# Medium_switch_HIGH_LOAD.net
KiCad netlist of a schematic drawn in EAGLE
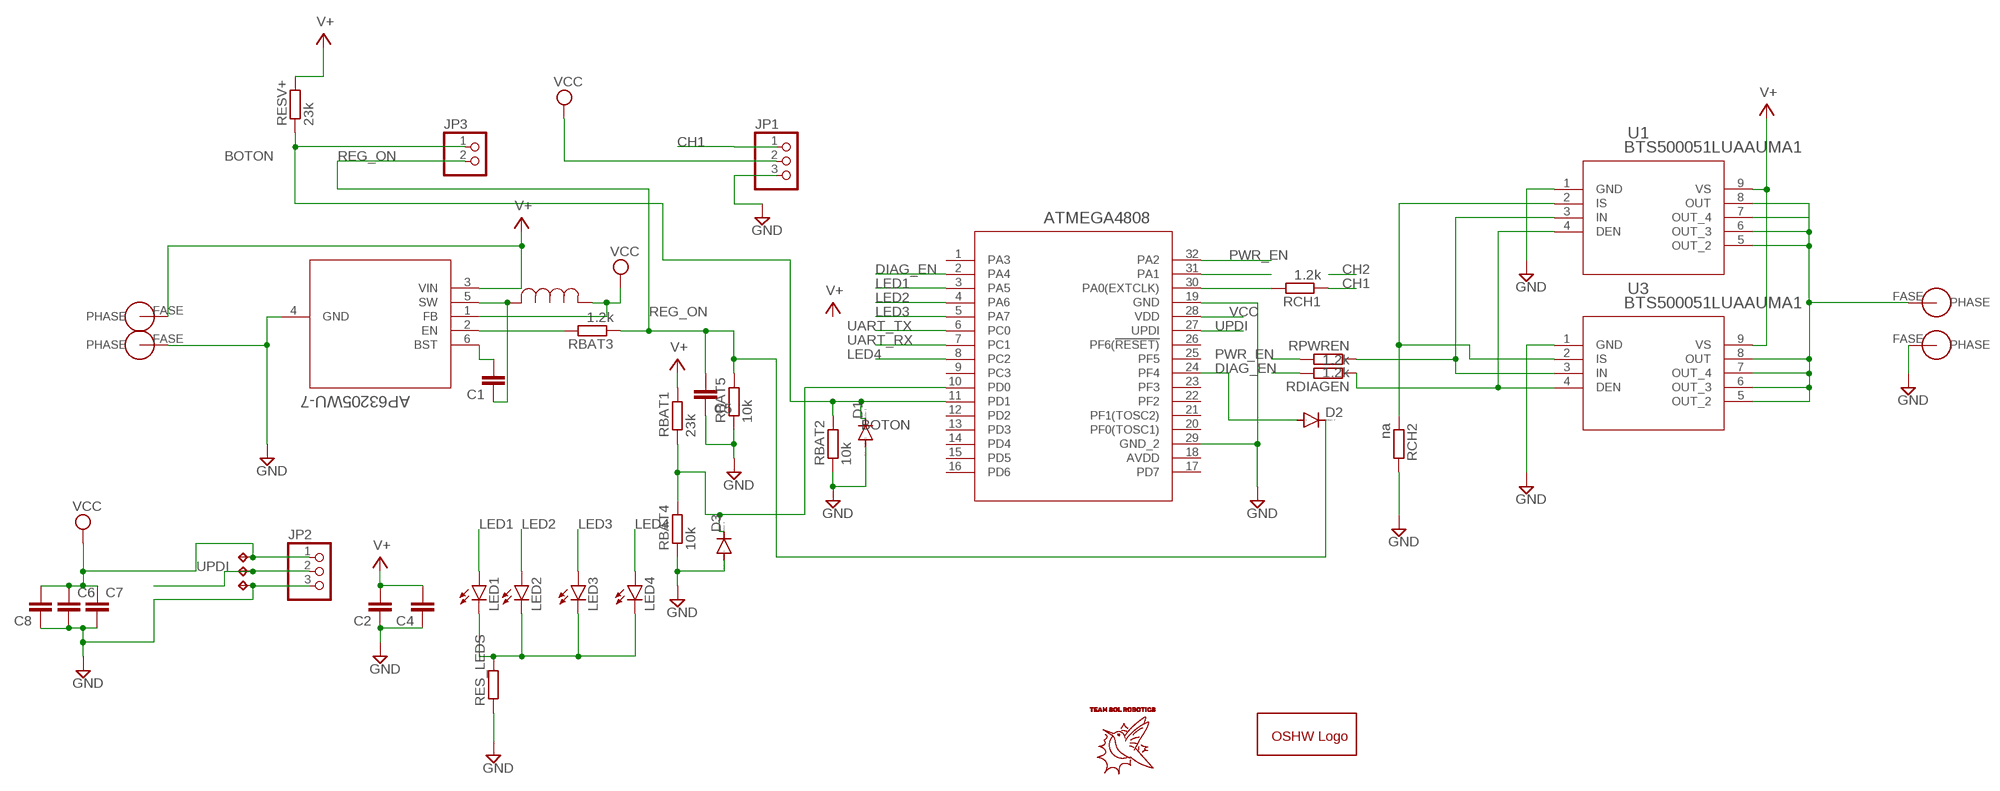
[diagram p0: schematic, sheet 1]

(export (version "E")
  (design (tool "Eeschema 10.0.6"))
  (components
    (comp (ref "BAT+")
      (value "PHASE")
      (footprint "eagle-import:POWEROUT")
      (libsource (lib "eagle-import") (part "PHASE"))
    )
    (comp (ref "C1")
      (value "C-EUC0402")
      (footprint "eagle-import:C0402")
      (libsource (lib "eagle-import") (part "C-EUC0402"))
    )
    (comp (ref "C2")
      (value "C-EUC1206")
      (footprint "eagle-import:C1206")
      (libsource (lib "eagle-import") (part "C-EUC1206"))
    )
    (comp (ref "C4")
      (value "C-EUC1206")
      (footprint "eagle-import:C1206")
      (libsource (lib "eagle-import") (part "C-EUC1206"))
    )
    (comp (ref "C5")
      (value "C-EUC0402")
      (footprint "eagle-import:C0402")
      (libsource (lib "eagle-import") (part "C-EUC0402"))
    )
    (comp (ref "C6")
      (value "C-EUC0805")
      (footprint "eagle-import:C0805")
      (libsource (lib "eagle-import") (part "C-EUC0805"))
    )
    (comp (ref "C7")
      (value "C-EUC0805")
      (footprint "eagle-import:C0805")
      (libsource (lib "eagle-import") (part "C-EUC0805"))
    )
    (comp (ref "C8")
      (value "C-EUC0402")
      (footprint "eagle-import:C0402")
      (libsource (lib "eagle-import") (part "C-EUC0402"))
    )
    (comp (ref "D1")
      (value "DIODE-MICROMELF-R")
      (footprint "eagle-import:MICROMELF-R")
      (libsource (lib "eagle-import") (part "DIODE-MICROMELF-R"))
    )
    (comp (ref "D2")
      (value "DIODE-MICROMELF-R")
      (footprint "eagle-import:MICROMELF-R")
      (libsource (lib "eagle-import") (part "DIODE-MICROMELF-R"))
    )
    (comp (ref "D3")
      (value "DIODE-MICROMELF-R")
      (footprint "eagle-import:MICROMELF-R")
      (libsource (lib "eagle-import") (part "DIODE-MICROMELF-R"))
    )
    (comp (ref "FASEA1")
      (value "PHASE")
      (footprint "eagle-import:POWEROUT")
      (libsource (lib "eagle-import") (part "PHASE"))
    )
    (comp (ref "FASEA3")
      (value "PHASE")
      (footprint "eagle-import:POWEROUT")
      (libsource (lib "eagle-import") (part "PHASE"))
    )
    (comp (ref "GOLD_ORB_SM1")
      (value "OSHWLOGOLOGO5MM")
      (footprint "eagle-import:OSHW_5MM")
      (libsource (lib "eagle-import") (part "OSHWLOGOLOGO5MM"))
    )
    (comp (ref "JP1")
      (value "PINHD-1X03_2.54-S")
      (footprint "eagle-import:1X03-S")
      (libsource (lib "eagle-import") (part "PINHD-1X03_2.54-S"))
    )
    (comp (ref "JP2")
      (value "PINHD-1X03_2.54-S")
      (footprint "eagle-import:1X03-S")
      (libsource (lib "eagle-import") (part "PINHD-1X03_2.54-S"))
    )
    (comp (ref "JP3")
      (value "PINHD-1X02_2.00")
      (footprint "eagle-import:1X02M")
      (libsource (lib "eagle-import") (part "PINHD-1X02_2.00"))
    )
    (comp (ref "LED1")
      (value "LEDSML0603")
      (footprint "eagle-import:SML0603")
      (libsource (lib "eagle-import") (part "LEDSML0603"))
    )
    (comp (ref "LED2")
      (value "LEDSML0603")
      (footprint "eagle-import:SML0603")
      (libsource (lib "eagle-import") (part "LEDSML0603"))
    )
    (comp (ref "LED3")
      (value "LEDSML0603")
      (footprint "eagle-import:SML0603")
      (libsource (lib "eagle-import") (part "LEDSML0603"))
    )
    (comp (ref "LED4")
      (value "LEDSML0603")
      (footprint "eagle-import:SML0603")
      (libsource (lib "eagle-import") (part "LEDSML0603"))
    )
    (comp (ref "OUTPUTPWR")
      (value "PHASE")
      (footprint "eagle-import:POWEROUT")
      (libsource (lib "eagle-import") (part "PHASE"))
    )
    (comp (ref "RBAT1")
      (value "23k")
      (footprint "eagle-import:R0603")
      (libsource (lib "eagle-import") (part "R-EU_R0603"))
    )
    (comp (ref "RBAT2")
      (value "10k")
      (footprint "eagle-import:R0603")
      (libsource (lib "eagle-import") (part "R-EU_R0603"))
    )
    (comp (ref "RBAT3")
      (value "1.2k")
      (footprint "eagle-import:R0603")
      (libsource (lib "eagle-import") (part "R-EU_R0603"))
    )
    (comp (ref "RBAT4")
      (value "10k")
      (footprint "eagle-import:R0603")
      (libsource (lib "eagle-import") (part "R-EU_R0603"))
    )
    (comp (ref "RBAT5")
      (value "10k")
      (footprint "eagle-import:R0603")
      (libsource (lib "eagle-import") (part "R-EU_R0603"))
    )
    (comp (ref "RCH1")
      (value "1.2k")
      (footprint "eagle-import:R0603")
      (libsource (lib "eagle-import") (part "R-EU_R0603"))
    )
    (comp (ref "RCH2")
      (value "na")
      (footprint "eagle-import:R0603")
      (libsource (lib "eagle-import") (part "R-EU_R0603"))
    )
    (comp (ref "RDIAGEN")
      (value "1.2k")
      (footprint "eagle-import:R0603")
      (libsource (lib "eagle-import") (part "R-EU_R0603"))
    )
    (comp (ref "RESV+")
      (value "23k")
      (footprint "eagle-import:R0603")
      (libsource (lib "eagle-import") (part "R-EU_R0603"))
    )
    (comp (ref "RES_LEDS")
      (value "R-EU_R0603")
      (footprint "eagle-import:R0603")
      (libsource (lib "eagle-import") (part "R-EU_R0603"))
    )
    (comp (ref "RPWREN")
      (value "1.2k")
      (footprint "eagle-import:R0603")
      (libsource (lib "eagle-import") (part "R-EU_R0603"))
    )
    (comp (ref "TP1")
      (value "TPTP13SQ")
      (footprint "eagle-import:TP13SQ")
      (libsource (lib "eagle-import") (part "TPTP13SQ"))
    )
    (comp (ref "TP2")
      (value "TPTP13SQ")
      (footprint "eagle-import:TP13SQ")
      (libsource (lib "eagle-import") (part "TPTP13SQ"))
    )
    (comp (ref "TP3")
      (value "TPTP13SQ")
      (footprint "eagle-import:TP13SQ")
      (libsource (lib "eagle-import") (part "TPTP13SQ"))
    )
    (comp (ref "U$1")
      (value "ATMEGA4808")
      (footprint "eagle-import:QFP80P900X900X120-32N")
      (libsource (lib "eagle-import") (part "ATMEGA4808"))
    )
    (comp (ref "U$3")
      (value "INDUCTOR4.7")
      (footprint "eagle-import:IND_NRS5030T100MMGJ_TAY")
      (libsource (lib "eagle-import") (part "INDUCTOR4.7"))
    )
    (comp (ref "U1")
      (value "BTS500051LUAAUMA1")
      (footprint "eagle-import:PG-HSOF-8_INF")
      (fields (field (name "COPYRIGHT") "Copyright (C) 2024 Ultra Librarian. All rights reserved."))
      (libsource (lib "eagle-import") (part "BTS500051LUAAUMA1"))
    )
    (comp (ref "U2")
      (value "AP63205WU-7")
      (footprint "eagle-import:SOIC_05WU-7_DIO")
      (fields (field (name "COPYRIGHT") "Copyright (C) 2018 Accelerated Designs. All rights reserved"))
      (libsource (lib "eagle-import") (part "AP63205WU-7"))
    )
    (comp (ref "U3")
      (value "BTS500051LUAAUMA1")
      (footprint "eagle-import:PG-HSOF-8_INF")
      (fields (field (name "COPYRIGHT") "Copyright (C) 2024 Ultra Librarian. All rights reserved."))
      (libsource (lib "eagle-import") (part "BTS500051LUAAUMA1"))
    )
  )
  (nets
    (net (code "1") (name "/AVDD") (class "Default")
      (node (ref "U$1") (pin "18") (pinfunction "AVDD_18") (pintype "power_in"))
    )
    (net (code "2") (name "/BOTON") (class "Default")
      (node (ref "D1") (pin "C") (pinfunction "C_C") (pintype "passive"))
      (node (ref "JP3") (pin "1") (pinfunction "1_1") (pintype "passive"))
      (node (ref "RBAT2") (pin "2") (pinfunction "2_2") (pintype "passive"))
      (node (ref "RESV+") (pin "1") (pinfunction "1_1") (pintype "passive"))
      (node (ref "U$1") (pin "11") (pinfunction "PD1_11") (pintype "bidirectional"))
    )
    (net (code "3") (name "/CH1") (class "Default")
      (node (ref "JP1") (pin "1") (pinfunction "1_1") (pintype "passive"))
      (node (ref "RCH1") (pin "1") (pinfunction "1_1") (pintype "passive"))
    )
    (net (code "5") (name "/DIAG_EN") (class "Default")
      (node (ref "RDIAGEN") (pin "2") (pinfunction "2_2") (pintype "passive"))
      (node (ref "U$1") (pin "2") (pinfunction "PA4_2") (pintype "bidirectional"))
    )
    (net (code "6") (name "/LED1") (class "Default")
      (node (ref "LED1") (pin "A") (pinfunction "A_A") (pintype "passive"))
      (node (ref "U$1") (pin "3") (pinfunction "PA5_3") (pintype "bidirectional"))
    )
    (net (code "7") (name "/LED2") (class "Default")
      (node (ref "LED2") (pin "A") (pinfunction "A_A") (pintype "passive"))
      (node (ref "U$1") (pin "4") (pinfunction "PA6_4") (pintype "bidirectional"))
    )
    (net (code "8") (name "/LED3") (class "Default")
      (node (ref "LED3") (pin "A") (pinfunction "A_A") (pintype "passive"))
      (node (ref "U$1") (pin "5") (pinfunction "PA7_5") (pintype "bidirectional"))
    )
    (net (code "9") (name "/LED4") (class "Default")
      (node (ref "LED4") (pin "A") (pinfunction "A_A") (pintype "passive"))
      (node (ref "U$1") (pin "8") (pinfunction "PC2_8") (pintype "bidirectional"))
    )
    (net (code "10") (name "/PWR_EN") (class "Default")
      (node (ref "RPWREN") (pin "2") (pinfunction "2_2") (pintype "passive"))
      (node (ref "U$1") (pin "32") (pinfunction "PA2_32") (pintype "bidirectional"))
    )
    (net (code "11") (name "/REG_ON") (class "Default")
      (node (ref "C5") (pin "2") (pinfunction "2_2") (pintype "passive"))
      (node (ref "D2") (pin "C") (pinfunction "C_C") (pintype "passive"))
      (node (ref "JP3") (pin "2") (pinfunction "2_2") (pintype "passive"))
      (node (ref "RBAT3") (pin "1") (pinfunction "1_1") (pintype "passive"))
      (node (ref "RBAT5") (pin "2") (pinfunction "2_2") (pintype "passive"))
    )
    (net (code "12") (name "/UART_RX") (class "Default")
      (node (ref "U$1") (pin "7") (pinfunction "PC1_7") (pintype "bidirectional"))
    )
    (net (code "13") (name "/UART_TX") (class "Default")
      (node (ref "U$1") (pin "6") (pinfunction "PC0_6") (pintype "bidirectional"))
    )
    (net (code "14") (name "/UPDI") (class "Default")
      (node (ref "JP2") (pin "2") (pinfunction "2_2") (pintype "passive"))
      (node (ref "TP3") (pin "TP") (pinfunction "TP_TP") (pintype "input"))
      (node (ref "U$1") (pin "27") (pinfunction "UPDI_27") (pintype "bidirectional"))
    )
    (net (code "15") (name "GND") (class "Default")
      (node (ref "C2") (pin "1") (pinfunction "1_1") (pintype "passive"))
      (node (ref "C4") (pin "1") (pinfunction "1_1") (pintype "passive"))
      (node (ref "C5") (pin "1") (pinfunction "1_1") (pintype "passive"))
      (node (ref "C6") (pin "2") (pinfunction "2_2") (pintype "passive"))
      (node (ref "C7") (pin "2") (pinfunction "2_2") (pintype "passive"))
      (node (ref "C8") (pin "1") (pinfunction "1_1") (pintype "passive"))
      (node (ref "D1") (pin "A") (pinfunction "A_A") (pintype "passive"))
      (node (ref "D3") (pin "A") (pinfunction "A_A") (pintype "passive"))
      (node (ref "FASEA1") (pin "FASE") (pinfunction "PHASE_FASE") (pintype "bidirectional"))
      (node (ref "FASEA3") (pin "FASE") (pinfunction "PHASE_FASE") (pintype "bidirectional"))
      (node (ref "JP1") (pin "3") (pinfunction "3_3") (pintype "passive"))
      (node (ref "JP2") (pin "3") (pinfunction "3_3") (pintype "passive"))
      (node (ref "RBAT2") (pin "1") (pinfunction "1_1") (pintype "passive"))
      (node (ref "RBAT4") (pin "1") (pinfunction "1_1") (pintype "passive"))
      (node (ref "RBAT5") (pin "1") (pinfunction "1_1") (pintype "passive"))
      (node (ref "RCH2") (pin "2") (pinfunction "2_2") (pintype "passive"))
      (node (ref "RES_LEDS") (pin "1") (pinfunction "1_1") (pintype "passive"))
      (node (ref "TP2") (pin "TP") (pinfunction "TP_TP") (pintype "input"))
      (node (ref "U$1") (pin "19") (pinfunction "GND_19") (pintype "passive"))
      (node (ref "U$1") (pin "29") (pinfunction "GND_2_29") (pintype "passive"))
      (node (ref "U1") (pin "1") (pinfunction "GND_1") (pintype "passive"))
      (node (ref "U2") (pin "4") (pinfunction "GND_4") (pintype "passive"))
      (node (ref "U3") (pin "1") (pinfunction "GND_1") (pintype "passive"))
    )
    (net (code "16") (name "Net-(LED1-PadC)") (class "Default")
      (node (ref "LED1") (pin "C") (pinfunction "C_C") (pintype "passive"))
      (node (ref "LED2") (pin "C") (pinfunction "C_C") (pintype "passive"))
      (node (ref "LED3") (pin "C") (pinfunction "C_C") (pintype "passive"))
      (node (ref "LED4") (pin "C") (pinfunction "C_C") (pintype "passive"))
      (node (ref "RES_LEDS") (pin "2") (pinfunction "2_2") (pintype "passive"))
    )
    (net (code "17") (name "Net-(OUTPUTPWR-PHASE)") (class "Default")
      (node (ref "OUTPUTPWR") (pin "FASE") (pinfunction "PHASE_FASE") (pintype "bidirectional"))
      (node (ref "U1") (pin "5") (pinfunction "OUT_2_5") (pintype "output"))
      (node (ref "U1") (pin "6") (pinfunction "OUT_3_6") (pintype "output"))
      (node (ref "U1") (pin "7") (pinfunction "OUT_4_7") (pintype "output"))
      (node (ref "U1") (pin "8") (pinfunction "OUT_8") (pintype "output"))
      (node (ref "U3") (pin "5") (pinfunction "OUT_2_5") (pintype "output"))
      (node (ref "U3") (pin "6") (pinfunction "OUT_3_6") (pintype "output"))
      (node (ref "U3") (pin "7") (pinfunction "OUT_4_7") (pintype "output"))
      (node (ref "U3") (pin "8") (pinfunction "OUT_8") (pintype "output"))
    )
    (net (code "18") (name "Net-(U$1-PA0(EXTCLK))") (class "Default")
      (node (ref "RCH1") (pin "2") (pinfunction "2_2") (pintype "passive"))
      (node (ref "U$1") (pin "30") (pinfunction "PA0(EXTCLK)_30") (pintype "bidirectional"))
    )
    (net (code "19") (name "Net-(U$1-PD0)") (class "Default")
      (node (ref "D3") (pin "C") (pinfunction "C_C") (pintype "passive"))
      (node (ref "RBAT1") (pin "1") (pinfunction "1_1") (pintype "passive"))
      (node (ref "RBAT4") (pin "2") (pinfunction "2_2") (pintype "passive"))
      (node (ref "U$1") (pin "10") (pinfunction "PD0_10") (pintype "bidirectional"))
    )
    (net (code "20") (name "Net-(U$1-PF4)") (class "Default")
      (node (ref "D2") (pin "A") (pinfunction "A_A") (pintype "passive"))
      (node (ref "U$1") (pin "24") (pinfunction "PF4_24") (pintype "bidirectional"))
    )
    (net (code "21") (name "Net-(U1-DEN)") (class "Default")
      (node (ref "RDIAGEN") (pin "1") (pinfunction "1_1") (pintype "passive"))
      (node (ref "U1") (pin "4") (pinfunction "DEN_4") (pintype "passive"))
      (node (ref "U3") (pin "4") (pinfunction "DEN_4") (pintype "passive"))
    )
    (net (code "22") (name "Net-(U1-IN)") (class "Default")
      (node (ref "RPWREN") (pin "1") (pinfunction "1_1") (pintype "passive"))
      (node (ref "U1") (pin "3") (pinfunction "IN_3") (pintype "input"))
      (node (ref "U3") (pin "3") (pinfunction "IN_3") (pintype "input"))
    )
    (net (code "23") (name "Net-(U1-IS)") (class "Default")
      (node (ref "RCH2") (pin "1") (pinfunction "1_1") (pintype "passive"))
      (node (ref "U1") (pin "2") (pinfunction "IS_2") (pintype "passive"))
      (node (ref "U3") (pin "2") (pinfunction "IS_2") (pintype "passive"))
    )
    (net (code "24") (name "Net-(U2-BST)") (class "Default")
      (node (ref "C1") (pin "2") (pinfunction "2_2") (pintype "passive"))
      (node (ref "U2") (pin "6") (pinfunction "BST_6") (pintype "passive"))
    )
    (net (code "25") (name "Net-(U2-EN)") (class "Default")
      (node (ref "RBAT3") (pin "2") (pinfunction "2_2") (pintype "passive"))
      (node (ref "U2") (pin "2") (pinfunction "EN_2") (pintype "passive"))
    )
    (net (code "26") (name "Net-(U2-SW)") (class "Default")
      (node (ref "C1") (pin "1") (pinfunction "1_1") (pintype "passive"))
      (node (ref "U$3") (pin "2") (pinfunction "2_2") (pintype "passive"))
      (node (ref "U2") (pin "5") (pinfunction "SW_5") (pintype "passive"))
    )
    (net (code "27") (name "V+") (class "Default")
      (node (ref "BAT+") (pin "FASE") (pinfunction "PHASE_FASE") (pintype "bidirectional"))
      (node (ref "C2") (pin "2") (pinfunction "2_2") (pintype "passive"))
      (node (ref "C4") (pin "2") (pinfunction "2_2") (pintype "passive"))
      (node (ref "RBAT1") (pin "2") (pinfunction "2_2") (pintype "passive"))
      (node (ref "RESV+") (pin "2") (pinfunction "2_2") (pintype "passive"))
      (node (ref "U1") (pin "9") (pinfunction "VS_9") (pintype "power_in"))
      (node (ref "U2") (pin "3") (pinfunction "VIN_3") (pintype "passive"))
      (node (ref "U3") (pin "9") (pinfunction "VS_9") (pintype "power_in"))
    )
    (net (code "28") (name "VCC") (class "Default")
      (node (ref "C6") (pin "1") (pinfunction "1_1") (pintype "passive"))
      (node (ref "C7") (pin "1") (pinfunction "1_1") (pintype "passive"))
      (node (ref "C8") (pin "2") (pinfunction "2_2") (pintype "passive"))
      (node (ref "JP1") (pin "2") (pinfunction "2_2") (pintype "passive"))
      (node (ref "JP2") (pin "1") (pinfunction "1_1") (pintype "passive"))
      (node (ref "TP1") (pin "TP") (pinfunction "TP_TP") (pintype "input"))
      (node (ref "U$1") (pin "28") (pinfunction "VDD_28") (pintype "power_in"))
      (node (ref "U$3") (pin "1") (pinfunction "1_1") (pintype "passive"))
      (node (ref "U2") (pin "1") (pinfunction "FB_1") (pintype "passive"))
    )
    (net (code "29") (name "unconnected-(U$1-PA1-Pad31)") (class "Default")
      (node (ref "U$1") (pin "31") (pinfunction "PA1_31") (pintype "bidirectional"))
    )
    (net (code "30") (name "unconnected-(U$1-PA3-Pad1)") (class "Default")
      (node (ref "U$1") (pin "1") (pinfunction "PA3_1") (pintype "bidirectional"))
    )
    (net (code "31") (name "unconnected-(U$1-PC3-Pad9)") (class "Default")
      (node (ref "U$1") (pin "9") (pinfunction "PC3_9") (pintype "bidirectional"))
    )
    (net (code "32") (name "unconnected-(U$1-PD2-Pad12)") (class "Default")
      (node (ref "U$1") (pin "12") (pinfunction "PD2_12") (pintype "bidirectional"))
    )
    (net (code "33") (name "unconnected-(U$1-PD3-Pad13)") (class "Default")
      (node (ref "U$1") (pin "13") (pinfunction "PD3_13") (pintype "bidirectional"))
    )
    (net (code "34") (name "unconnected-(U$1-PD4-Pad14)") (class "Default")
      (node (ref "U$1") (pin "14") (pinfunction "PD4_14") (pintype "bidirectional"))
    )
    (net (code "35") (name "unconnected-(U$1-PD5-Pad15)") (class "Default")
      (node (ref "U$1") (pin "15") (pinfunction "PD5_15") (pintype "bidirectional"))
    )
    (net (code "36") (name "unconnected-(U$1-PD6-Pad16)") (class "Default")
      (node (ref "U$1") (pin "16") (pinfunction "PD6_16") (pintype "bidirectional"))
    )
    (net (code "37") (name "unconnected-(U$1-PD7-Pad17)") (class "Default")
      (node (ref "U$1") (pin "17") (pinfunction "PD7_17") (pintype "bidirectional"))
    )
    (net (code "38") (name "unconnected-(U$1-PF0(TOSC1)-Pad20)") (class "Default")
      (node (ref "U$1") (pin "20") (pinfunction "PF0(TOSC1)_20") (pintype "bidirectional"))
    )
    (net (code "39") (name "unconnected-(U$1-PF1(TOSC2)-Pad21)") (class "Default")
      (node (ref "U$1") (pin "21") (pinfunction "PF1(TOSC2)_21") (pintype "bidirectional"))
    )
    (net (code "40") (name "unconnected-(U$1-PF2-Pad22)") (class "Default")
      (node (ref "U$1") (pin "22") (pinfunction "PF2_22") (pintype "bidirectional"))
    )
    (net (code "41") (name "unconnected-(U$1-PF3-Pad23)") (class "Default")
      (node (ref "U$1") (pin "23") (pinfunction "PF3_23") (pintype "bidirectional"))
    )
    (net (code "42") (name "unconnected-(U$1-PF5-Pad25)") (class "Default")
      (node (ref "U$1") (pin "25") (pinfunction "PF5_25") (pintype "bidirectional"))
    )
    (net (code "43") (name "unconnected-(U$1-PF6(~{RESET})-Pad26)") (class "Default")
      (node (ref "U$1") (pin "26") (pinfunction "PF6(~{RESET})_26") (pintype "bidirectional"))
    )
  )
)
